# pH-metr.net
KiCad netlist of a schematic drawn in EAGLE
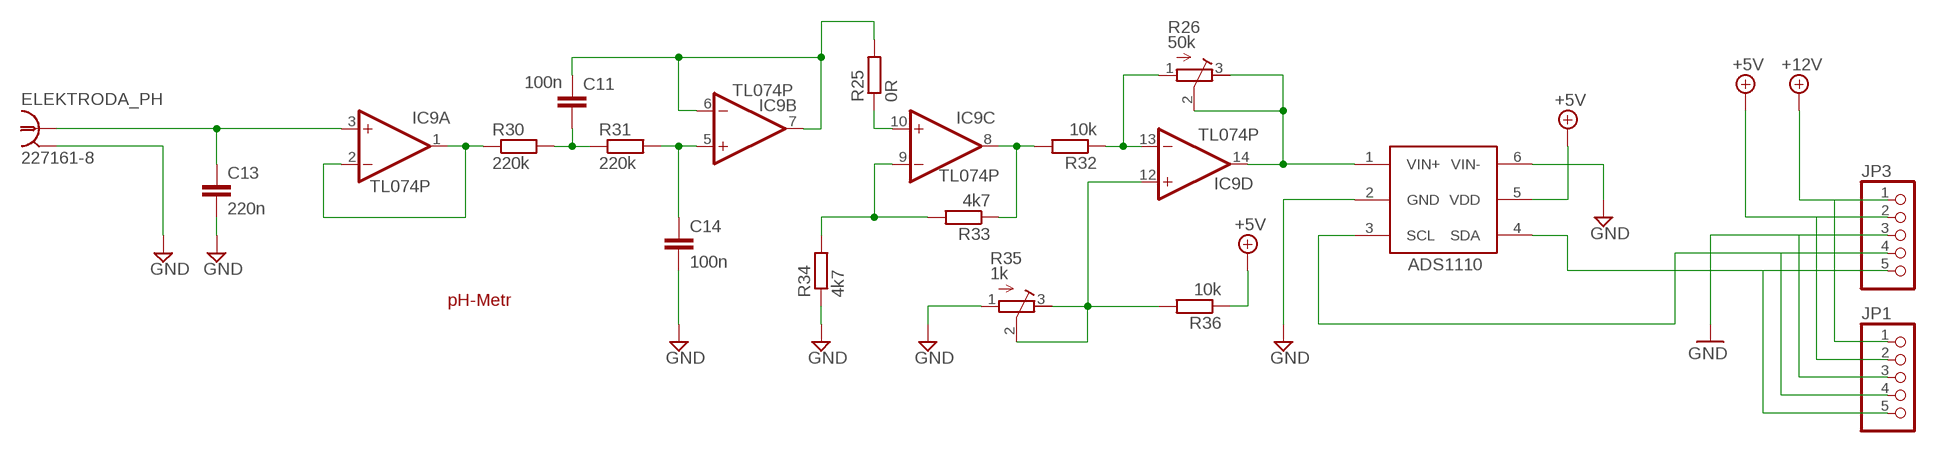
[diagram p0: schematic, sheet 1]

(export (version "E")
  (design (tool "Eeschema 10.0.6"))
  (components
    (comp (ref "C11")
      (value "100n")
      (footprint "eagle-import:C1206")
      (libsource (lib "eagle-import") (part "C-EUC1206"))
    )
    (comp (ref "C13")
      (value "220n")
      (footprint "eagle-import:C050-025X075")
      (libsource (lib "eagle-import") (part "C-EU050-025X075"))
    )
    (comp (ref "C14")
      (value "100n")
      (footprint "eagle-import:C1206")
      (libsource (lib "eagle-import") (part "C-EUC1206"))
    )
    (comp (ref "ELEKTRODA_PH")
      (value "227161-8")
      (footprint "eagle-import:AMP_227161")
      (libsource (lib "eagle-import") (part "?227161-8"))
    )
    (comp (ref "IC2")
      (value "ADS1110")
      (footprint "eagle-import:SOT-23-6")
      (libsource (lib "eagle-import") (part "ADS1110"))
    )
    (comp (ref "IC9")
      (value "TL074P")
      (footprint "eagle-import:DIL14")
      (libsource (lib "eagle-import") (part "TL074P"))
    )
    (comp (ref "JP1")
      (value "PINHD-1X5/90")
      (footprint "eagle-import:1X05_90")
      (libsource (lib "eagle-import") (part "PINHD-1X5/90"))
    )
    (comp (ref "JP3")
      (value "PINHD-1X5/90")
      (footprint "eagle-import:1X05_90")
      (libsource (lib "eagle-import") (part "PINHD-1X5/90"))
    )
    (comp (ref "R25")
      (value "0R")
      (footprint "eagle-import:R1206")
      (libsource (lib "eagle-import") (part "R-EU_R1206"))
    )
    (comp (ref "R26")
      (value "50k")
      (footprint "eagle-import:RTRIM64X")
      (libsource (lib "eagle-import") (part "R-TRIMM64X"))
    )
    (comp (ref "R30")
      (value "220k")
      (footprint "eagle-import:R1206")
      (libsource (lib "eagle-import") (part "R-EU_R1206"))
    )
    (comp (ref "R31")
      (value "220k")
      (footprint "eagle-import:R1206")
      (libsource (lib "eagle-import") (part "R-EU_R1206"))
    )
    (comp (ref "R32")
      (value "10k")
      (footprint "eagle-import:R1206")
      (libsource (lib "eagle-import") (part "R-EU_R1206"))
    )
    (comp (ref "R33")
      (value "4k7")
      (footprint "eagle-import:R1206")
      (libsource (lib "eagle-import") (part "R-EU_R1206"))
    )
    (comp (ref "R34")
      (value "4k7")
      (footprint "eagle-import:R1206")
      (libsource (lib "eagle-import") (part "R-EU_R1206"))
    )
    (comp (ref "R35")
      (value "1k")
      (footprint "eagle-import:RTRIM64X")
      (libsource (lib "eagle-import") (part "R-TRIMM64X"))
    )
    (comp (ref "R36")
      (value "10k")
      (footprint "eagle-import:R1206")
      (libsource (lib "eagle-import") (part "R-EU_R1206"))
    )
  )
  (nets
    (net (code "1") (name "+5V") (class "Default")
      (node (ref "IC2") (pin "5") (pinfunction "VDD_5") (pintype "bidirectional"))
      (node (ref "JP1") (pin "2") (pinfunction "2_2") (pintype "passive"))
      (node (ref "JP3") (pin "2") (pinfunction "2_2") (pintype "passive"))
      (node (ref "R36") (pin "1") (pinfunction "1_1") (pintype "passive"))
    )
    (net (code "2") (name "+12V") (class "Default")
      (node (ref "JP1") (pin "1") (pinfunction "1_1") (pintype "passive"))
      (node (ref "JP3") (pin "1") (pinfunction "1_1") (pintype "passive"))
    )
    (net (code "3") (name "GND") (class "Default")
      (node (ref "C13") (pin "2") (pinfunction "2_2") (pintype "passive"))
      (node (ref "C14") (pin "2") (pinfunction "2_2") (pintype "passive"))
      (node (ref "ELEKTRODA_PH") (pin "2") (pinfunction "GND_2") (pintype "power_in"))
      (node (ref "IC2") (pin "2") (pinfunction "GND_2") (pintype "bidirectional"))
      (node (ref "IC2") (pin "6") (pinfunction "VIN-_6") (pintype "bidirectional"))
      (node (ref "JP1") (pin "3") (pinfunction "3_3") (pintype "passive"))
      (node (ref "JP3") (pin "3") (pinfunction "3_3") (pintype "passive"))
      (node (ref "R34") (pin "1") (pinfunction "1_1") (pintype "passive"))
      (node (ref "R35") (pin "1") (pinfunction "A_1") (pintype "passive"))
    )
    (net (code "4") (name "Net-(C11-Pad2)") (class "Default")
      (node (ref "C11") (pin "2") (pinfunction "2_2") (pintype "passive"))
      (node (ref "R30") (pin "2") (pinfunction "2_2") (pintype "passive"))
      (node (ref "R31") (pin "1") (pinfunction "1_1") (pintype "passive"))
    )
    (net (code "5") (name "Net-(IC2-SCL)") (class "Default")
      (node (ref "IC2") (pin "3") (pinfunction "SCL_3") (pintype "bidirectional"))
      (node (ref "JP1") (pin "4") (pinfunction "4_4") (pintype "passive"))
      (node (ref "JP3") (pin "4") (pinfunction "4_4") (pintype "passive"))
    )
    (net (code "6") (name "Net-(IC2-SDA)") (class "Default")
      (node (ref "IC2") (pin "4") (pinfunction "SDA_4") (pintype "bidirectional"))
      (node (ref "JP1") (pin "5") (pinfunction "5_5") (pintype "passive"))
      (node (ref "JP3") (pin "5") (pinfunction "5_5") (pintype "passive"))
    )
    (net (code "7") (name "Net-(IC2-VIN+)") (class "Default")
      (node (ref "IC2") (pin "1") (pinfunction "VIN+_1") (pintype "bidirectional"))
      (node (ref "IC9") (pin "14") (pinfunction "OUT_14") (pintype "output"))
      (node (ref "R26") (pin "2") (pinfunction "S_2") (pintype "passive"))
      (node (ref "R26") (pin "3") (pinfunction "E_3") (pintype "passive"))
    )
    (net (code "8") (name "Net-(IC9A-+IN)") (class "Default")
      (node (ref "C13") (pin "1") (pinfunction "1_1") (pintype "passive"))
      (node (ref "ELEKTRODA_PH") (pin "1") (pinfunction "1_1") (pintype "passive"))
      (node (ref "IC9") (pin "3") (pinfunction "+IN_3") (pintype "input"))
    )
    (net (code "9") (name "Net-(IC9A--IN)") (class "Default")
      (node (ref "IC9") (pin "1") (pinfunction "OUT_1") (pintype "output"))
      (node (ref "IC9") (pin "2") (pinfunction "-IN_2") (pintype "input"))
      (node (ref "R30") (pin "1") (pinfunction "1_1") (pintype "passive"))
    )
    (net (code "10") (name "Net-(IC9B-+IN)") (class "Default")
      (node (ref "C14") (pin "1") (pinfunction "1_1") (pintype "passive"))
      (node (ref "IC9") (pin "5") (pinfunction "+IN_5") (pintype "input"))
      (node (ref "R31") (pin "2") (pinfunction "2_2") (pintype "passive"))
    )
    (net (code "11") (name "Net-(IC9B--IN)") (class "Default")
      (node (ref "C11") (pin "1") (pinfunction "1_1") (pintype "passive"))
      (node (ref "IC9") (pin "6") (pinfunction "-IN_6") (pintype "input"))
      (node (ref "IC9") (pin "7") (pinfunction "OUT_7") (pintype "output"))
      (node (ref "R25") (pin "2") (pinfunction "2_2") (pintype "passive"))
    )
    (net (code "12") (name "Net-(IC9C-+IN)") (class "Default")
      (node (ref "IC9") (pin "10") (pinfunction "+IN_10") (pintype "input"))
      (node (ref "R25") (pin "1") (pinfunction "1_1") (pintype "passive"))
    )
    (net (code "13") (name "Net-(IC9C--IN)") (class "Default")
      (node (ref "IC9") (pin "9") (pinfunction "-IN_9") (pintype "input"))
      (node (ref "R33") (pin "2") (pinfunction "2_2") (pintype "passive"))
      (node (ref "R34") (pin "2") (pinfunction "2_2") (pintype "passive"))
    )
    (net (code "14") (name "Net-(IC9C-OUT)") (class "Default")
      (node (ref "IC9") (pin "8") (pinfunction "OUT_8") (pintype "output"))
      (node (ref "R32") (pin "2") (pinfunction "2_2") (pintype "passive"))
      (node (ref "R33") (pin "1") (pinfunction "1_1") (pintype "passive"))
    )
    (net (code "15") (name "Net-(IC9D-+IN)") (class "Default")
      (node (ref "IC9") (pin "12") (pinfunction "+IN_12") (pintype "input"))
      (node (ref "R35") (pin "2") (pinfunction "S_2") (pintype "passive"))
      (node (ref "R35") (pin "3") (pinfunction "E_3") (pintype "passive"))
      (node (ref "R36") (pin "2") (pinfunction "2_2") (pintype "passive"))
    )
    (net (code "16") (name "Net-(IC9D--IN)") (class "Default")
      (node (ref "IC9") (pin "13") (pinfunction "-IN_13") (pintype "input"))
      (node (ref "R26") (pin "1") (pinfunction "A_1") (pintype "passive"))
      (node (ref "R32") (pin "1") (pinfunction "1_1") (pintype "passive"))
    )
  )
)
